# untitled2.net
KiCad netlist of a schematic drawn in EAGLE
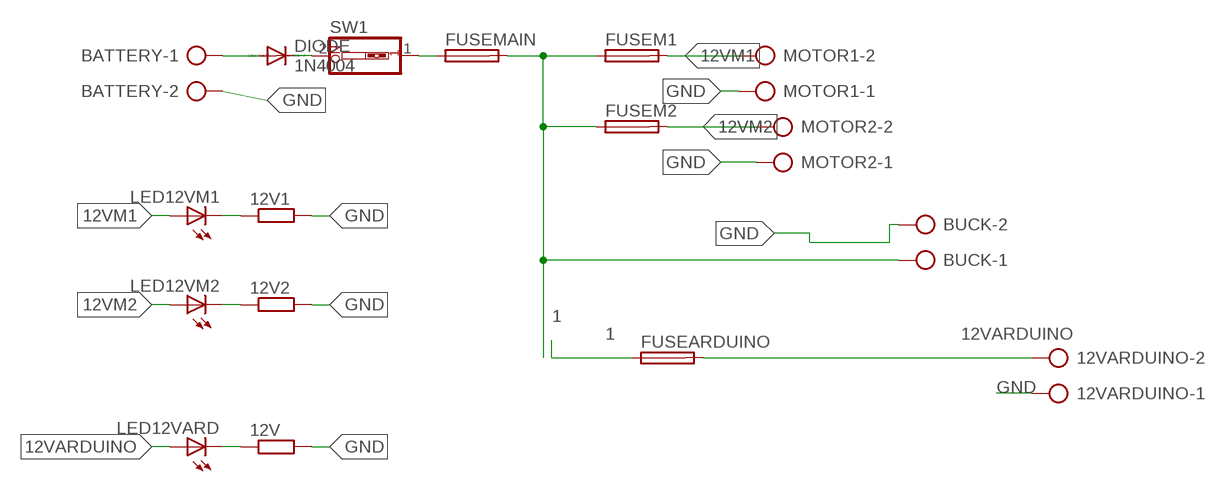
[diagram p0: schematic, sheet 1]

(export (version "E")
  (design (tool "Eeschema 10.0.6"))
  (components
    (comp (ref "12V")
      (value "R-EU_0204/7")
      (footprint "eagle-import:0204_7")
      (libsource (lib "eagle-import") (part "R-EU_0204/7"))
    )
    (comp (ref "12V1")
      (value "R-EU_0204/7")
      (footprint "eagle-import:0204_7")
      (libsource (lib "eagle-import") (part "R-EU_0204/7"))
    )
    (comp (ref "12V2")
      (value "R-EU_0204/7")
      (footprint "eagle-import:0204_7")
      (libsource (lib "eagle-import") (part "R-EU_0204/7"))
    )
    (comp (ref "12VARDUINO")
      (value "AK500/2-H")
      (footprint "eagle-import:AK500_2-H")
      (libsource (lib "eagle-import") (part "AK500/2-H"))
    )
    (comp (ref "BATTERY")
      (value "AK500/2-H")
      (footprint "eagle-import:AK500_2-H")
      (libsource (lib "eagle-import") (part "AK500/2-H"))
    )
    (comp (ref "BUCK")
      (value "AK500/2-H")
      (footprint "eagle-import:AK500_2-H")
      (libsource (lib "eagle-import") (part "AK500/2-H"))
    )
    (comp (ref "DIODE")
      (value "1N4004")
      (footprint "eagle-import:DO41-10")
      (libsource (lib "eagle-import") (part "1N4004"))
    )
    (comp (ref "FUSEARDUINO")
      (value "SH22,5")
      (footprint "eagle-import:SH22,5")
      (fields (field (name "MF") "SCHURTER") (field (name "MPN") "0031.8201"))
      (libsource (lib "eagle-import") (part "SH22,5"))
    )
    (comp (ref "FUSEM1")
      (value "SH22,5")
      (footprint "eagle-import:SH22,5")
      (fields (field (name "MF") "SCHURTER") (field (name "MPN") "0031.8201"))
      (libsource (lib "eagle-import") (part "SH22,5"))
    )
    (comp (ref "FUSEM2")
      (value "SH22,5")
      (footprint "eagle-import:SH22,5")
      (fields (field (name "MF") "SCHURTER") (field (name "MPN") "0031.8201"))
      (libsource (lib "eagle-import") (part "SH22,5"))
    )
    (comp (ref "FUSEMAIN")
      (value "SH22,5")
      (footprint "eagle-import:SH22,5")
      (fields (field (name "MF") "SCHURTER") (field (name "MPN") "0031.8201"))
      (libsource (lib "eagle-import") (part "SH22,5"))
    )
    (comp (ref "LED12VARD")
      (value "LEDLSU260")
      (footprint "eagle-import:LSU260")
      (libsource (lib "eagle-import") (part "LEDLSU260"))
    )
    (comp (ref "LED12VM1")
      (value "LEDLSU260")
      (footprint "eagle-import:LSU260")
      (libsource (lib "eagle-import") (part "LEDLSU260"))
    )
    (comp (ref "LED12VM2")
      (value "LEDLSU260")
      (footprint "eagle-import:LSU260")
      (libsource (lib "eagle-import") (part "LEDLSU260"))
    )
    (comp (ref "MOTOR1")
      (value "AK500/2-H")
      (footprint "eagle-import:AK500_2-H")
      (libsource (lib "eagle-import") (part "AK500/2-H"))
    )
    (comp (ref "MOTOR2")
      (value "AK500/2-H")
      (footprint "eagle-import:AK500_2-H")
      (libsource (lib "eagle-import") (part "AK500/2-H"))
    )
    (comp (ref "SW1")
      (value "SW_DIP-1")
      (footprint "eagle-import:EDG-01")
      (libsource (lib "eagle-import") (part "SW_DIP-1"))
    )
  )
  (nets
    (net (code "1") (name "/1") (class "Default")
      (node (ref "BUCK") (pin "1") (pinfunction "KL_1") (pintype "passive"))
      (node (ref "FUSEARDUINO") (pin "1") (pinfunction "1_1") (pintype "passive"))
      (node (ref "FUSEM1") (pin "1") (pinfunction "1_1") (pintype "passive"))
      (node (ref "FUSEM2") (pin "1") (pinfunction "1_1") (pintype "passive"))
      (node (ref "FUSEMAIN") (pin "2") (pinfunction "2_2") (pintype "passive"))
    )
    (net (code "2") (name "12VARDUINO") (class "Default")
      (node (ref "12VARDUINO") (pin "2") (pinfunction "KL_2") (pintype "passive"))
      (node (ref "FUSEARDUINO") (pin "2") (pinfunction "2_2") (pintype "passive"))
      (node (ref "LED12VARD") (pin "A") (pinfunction "A_A") (pintype "passive"))
    )
    (net (code "3") (name "12VM1") (class "Default")
      (node (ref "FUSEM1") (pin "2") (pinfunction "2_2") (pintype "passive"))
      (node (ref "LED12VM1") (pin "A") (pinfunction "A_A") (pintype "passive"))
      (node (ref "MOTOR1") (pin "2") (pinfunction "KL_2") (pintype "passive"))
    )
    (net (code "4") (name "12VM2") (class "Default")
      (node (ref "FUSEM2") (pin "2") (pinfunction "2_2") (pintype "passive"))
      (node (ref "LED12VM2") (pin "A") (pinfunction "A_A") (pintype "passive"))
      (node (ref "MOTOR2") (pin "2") (pinfunction "KL_2") (pintype "passive"))
    )
    (net (code "5") (name "GND") (class "Default")
      (node (ref "12V") (pin "2") (pinfunction "2_2") (pintype "passive"))
      (node (ref "12V1") (pin "2") (pinfunction "2_2") (pintype "passive"))
      (node (ref "12V2") (pin "2") (pinfunction "2_2") (pintype "passive"))
      (node (ref "12VARDUINO") (pin "1") (pinfunction "KL_1") (pintype "passive"))
      (node (ref "BATTERY") (pin "2") (pinfunction "KL_2") (pintype "passive"))
      (node (ref "BUCK") (pin "2") (pinfunction "KL_2") (pintype "passive"))
      (node (ref "MOTOR1") (pin "1") (pinfunction "KL_1") (pintype "passive"))
      (node (ref "MOTOR2") (pin "1") (pinfunction "KL_1") (pintype "passive"))
    )
    (net (code "6") (name "Net-(BATTERYA-KL)") (class "Default")
      (node (ref "BATTERY") (pin "1") (pinfunction "KL_1") (pintype "passive"))
      (node (ref "DIODE") (pin "A") (pinfunction "A_A") (pintype "passive"))
    )
    (net (code "7") (name "Net-(DIODE-PadC)") (class "Default")
      (node (ref "DIODE") (pin "C") (pinfunction "C_C") (pintype "passive"))
      (node (ref "SW1") (pin "2") (pinfunction "2_2") (pintype "passive"))
    )
    (net (code "8") (name "Net-(FUSEMAIN-Pad1)") (class "Default")
      (node (ref "FUSEMAIN") (pin "1") (pinfunction "1_1") (pintype "passive"))
      (node (ref "SW1") (pin "1") (pinfunction "1_1") (pintype "passive"))
    )
    (net (code "9") (name "Net-(LED12VARD-C)") (class "Default")
      (node (ref "12V") (pin "1") (pinfunction "1_1") (pintype "passive"))
      (node (ref "LED12VARD") (pin "K") (pinfunction "C_K") (pintype "passive"))
    )
    (net (code "10") (name "Net-(LED12VM1-C)") (class "Default")
      (node (ref "12V1") (pin "1") (pinfunction "1_1") (pintype "passive"))
      (node (ref "LED12VM1") (pin "K") (pinfunction "C_K") (pintype "passive"))
    )
    (net (code "11") (name "Net-(LED12VM2-C)") (class "Default")
      (node (ref "12V2") (pin "1") (pinfunction "1_1") (pintype "passive"))
      (node (ref "LED12VM2") (pin "K") (pinfunction "C_K") (pintype "passive"))
    )
  )
)
